# Control.net
KiCad netlist of a schematic drawn in Altium Designer
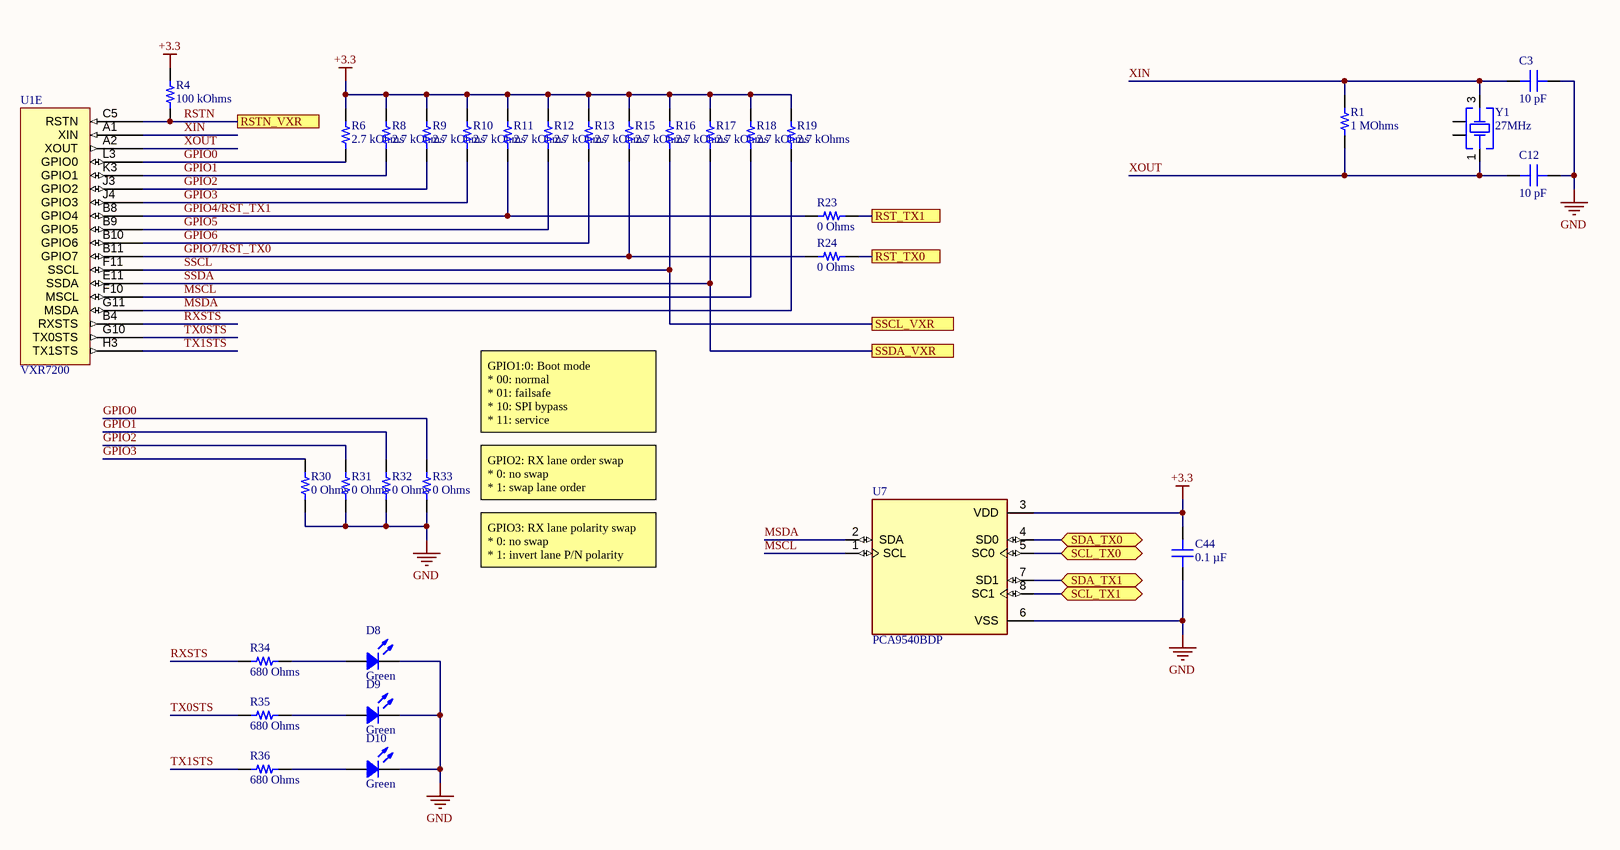
[diagram p0: Control.SchDoc]

(export (version "E")
  (design (tool "Eeschema 10.0.6"))
  (components
    (comp (ref "C3")
      (value "10 pF")
      (footprint "CAP 0201_0603")
      (description "CAP CER 10PF 25V C0G/NP0 0201")
      (fields
        (field (name "PART NUMBER") "GRM0335C1E100JA01D")
        (field (name "MANUFACTURER") "Murata Electronics")
      )
      (libsource (lib "Celestial Altium Library - altium_library") (part "Capacitor"))
    )
    (comp (ref "C12")
      (value "10 pF")
      (footprint "CAP 0201_0603")
      (description "CAP CER 10PF 25V C0G/NP0 0201")
      (fields
        (field (name "PART NUMBER") "GRM0335C1E100JA01D")
        (field (name "MANUFACTURER") "Murata Electronics")
      )
      (libsource (lib "Celestial Altium Library - altium_library") (part "Capacitor"))
    )
    (comp (ref "C44")
      (value "0.1 µF")
      (footprint "CAP 0201_0603")
      (description "CAP CER 0.1UF 25V X5R 0201")
      (fields
        (field (name "PART NUMBER") "GRM033R61E104KE14D")
        (field (name "MANUFACTURER") "Murata Electronics")
      )
      (libsource (lib "Celestial Altium Library - altium_library") (part "Capacitor"))
    )
    (comp (ref "D8")
      (value "Green")
      (footprint "LED 0603_1608 GREEN")
      (description "LED GREEN DIFFUSED 0603 SMD")
      (fields (field (name "PART NUMBER") "150060GS55040") (field (name "MANUFACTURER") "Würth Elektronik"))
      (libsource (lib "Celestial Altium Library - altium_library") (part "LED"))
    )
    (comp (ref "D9")
      (value "Green")
      (footprint "LED 0603_1608 GREEN")
      (description "LED GREEN DIFFUSED 0603 SMD")
      (fields (field (name "PART NUMBER") "150060GS55040") (field (name "MANUFACTURER") "Würth Elektronik"))
      (libsource (lib "Celestial Altium Library - altium_library") (part "LED"))
    )
    (comp (ref "D10")
      (value "Green")
      (footprint "LED 0603_1608 GREEN")
      (description "LED GREEN DIFFUSED 0603 SMD")
      (fields (field (name "PART NUMBER") "150060GS55040") (field (name "MANUFACTURER") "Würth Elektronik"))
      (libsource (lib "Celestial Altium Library - altium_library") (part "LED"))
    )
    (comp (ref "R1")
      (value "1 MOhms")
      (footprint "RES 0201_0603")
      (description "RES SMD 1M OHM 1% 1/20W 0201")
      (fields (field (name "PART NUMBER") "CRCW02011M00FKED") (field (name "MANUFACTURER") "Vishay Dale"))
      (libsource (lib "Celestial Altium Library - altium_library") (part "Resistor"))
    )
    (comp (ref "R4")
      (value "100 kOhms")
      (footprint "RES 0201_0603")
      (description "RES 100K OHM 1% 1/20W 0201 SMD")
      (fields
        (field (name "PART NUMBER") "ERJ-U01F1003C")
        (field (name "MANUFACTURER") "Panasonic Electronic Components")
      )
      (libsource (lib "Celestial Altium Library - altium_library") (part "Resistor"))
    )
    (comp (ref "R6")
      (value "2.7 kOhms")
      (footprint "RES 0201_0603")
      (description "RES 2.7K OHM 5% 1/20W 0201 SMD")
      (fields
        (field (name "PART NUMBER") "ERJ-U01J272C")
        (field (name "MANUFACTURER") "Panasonic Electronic Components")
      )
      (libsource (lib "Celestial Altium Library - altium_library") (part "Resistor"))
    )
    (comp (ref "R8")
      (value "2.7 kOhms")
      (footprint "RES 0201_0603")
      (description "RES 2.7K OHM 5% 1/20W 0201 SMD")
      (fields
        (field (name "PART NUMBER") "ERJ-U01J272C")
        (field (name "MANUFACTURER") "Panasonic Electronic Components")
      )
      (libsource (lib "Celestial Altium Library - altium_library") (part "Resistor"))
    )
    (comp (ref "R9")
      (value "2.7 kOhms")
      (footprint "RES 0201_0603")
      (description "RES 2.7K OHM 5% 1/20W 0201 SMD")
      (fields
        (field (name "PART NUMBER") "ERJ-U01J272C")
        (field (name "MANUFACTURER") "Panasonic Electronic Components")
      )
      (libsource (lib "Celestial Altium Library - altium_library") (part "Resistor"))
    )
    (comp (ref "R10")
      (value "2.7 kOhms")
      (footprint "RES 0201_0603")
      (description "RES 2.7K OHM 5% 1/20W 0201 SMD")
      (fields
        (field (name "PART NUMBER") "ERJ-U01J272C")
        (field (name "MANUFACTURER") "Panasonic Electronic Components")
      )
      (libsource (lib "Celestial Altium Library - altium_library") (part "Resistor"))
    )
    (comp (ref "R11")
      (value "2.7 kOhms")
      (footprint "RES 0201_0603")
      (description "RES 2.7K OHM 5% 1/20W 0201 SMD")
      (fields
        (field (name "PART NUMBER") "ERJ-U01J272C")
        (field (name "MANUFACTURER") "Panasonic Electronic Components")
      )
      (libsource (lib "Celestial Altium Library - altium_library") (part "Resistor"))
    )
    (comp (ref "R12")
      (value "2.7 kOhms")
      (footprint "RES 0201_0603")
      (description "RES 2.7K OHM 5% 1/20W 0201 SMD")
      (fields
        (field (name "PART NUMBER") "ERJ-U01J272C")
        (field (name "MANUFACTURER") "Panasonic Electronic Components")
      )
      (libsource (lib "Celestial Altium Library - altium_library") (part "Resistor"))
    )
    (comp (ref "R13")
      (value "2.7 kOhms")
      (footprint "RES 0201_0603")
      (description "RES 2.7K OHM 5% 1/20W 0201 SMD")
      (fields
        (field (name "PART NUMBER") "ERJ-U01J272C")
        (field (name "MANUFACTURER") "Panasonic Electronic Components")
      )
      (libsource (lib "Celestial Altium Library - altium_library") (part "Resistor"))
    )
    (comp (ref "R15")
      (value "2.7 kOhms")
      (footprint "RES 0201_0603")
      (description "RES 2.7K OHM 5% 1/20W 0201 SMD")
      (fields
        (field (name "PART NUMBER") "ERJ-U01J272C")
        (field (name "MANUFACTURER") "Panasonic Electronic Components")
      )
      (libsource (lib "Celestial Altium Library - altium_library") (part "Resistor"))
    )
    (comp (ref "R16")
      (value "2.7 kOhms")
      (footprint "RES 0201_0603")
      (description "RES 2.7K OHM 5% 1/20W 0201 SMD")
      (fields
        (field (name "PART NUMBER") "ERJ-U01J272C")
        (field (name "MANUFACTURER") "Panasonic Electronic Components")
      )
      (libsource (lib "Celestial Altium Library - altium_library") (part "Resistor"))
    )
    (comp (ref "R17")
      (value "2.7 kOhms")
      (footprint "RES 0201_0603")
      (description "RES 2.7K OHM 5% 1/20W 0201 SMD")
      (fields
        (field (name "PART NUMBER") "ERJ-U01J272C")
        (field (name "MANUFACTURER") "Panasonic Electronic Components")
      )
      (libsource (lib "Celestial Altium Library - altium_library") (part "Resistor"))
    )
    (comp (ref "R18")
      (value "2.7 kOhms")
      (footprint "RES 0201_0603")
      (description "RES 2.7K OHM 5% 1/20W 0201 SMD")
      (fields
        (field (name "PART NUMBER") "ERJ-U01J272C")
        (field (name "MANUFACTURER") "Panasonic Electronic Components")
      )
      (libsource (lib "Celestial Altium Library - altium_library") (part "Resistor"))
    )
    (comp (ref "R19")
      (value "2.7 kOhms")
      (footprint "RES 0201_0603")
      (description "RES 2.7K OHM 5% 1/20W 0201 SMD")
      (fields
        (field (name "PART NUMBER") "ERJ-U01J272C")
        (field (name "MANUFACTURER") "Panasonic Electronic Components")
      )
      (libsource (lib "Celestial Altium Library - altium_library") (part "Resistor"))
    )
    (comp (ref "R23")
      (value "0 Ohms")
      (footprint "RES 0402_1005")
      (description "RESISTOR 0402 JUMPER ZERO OHM")
      (fields (field (name "PART NUMBER") "AC0402FR-070RL") (field (name "MANUFACTURER") "Yageo"))
      (libsource (lib "Celestial Altium Library - altium_library") (part "Resistor"))
    )
    (comp (ref "R24")
      (value "0 Ohms")
      (footprint "RES 0402_1005")
      (description "RESISTOR 0402 JUMPER ZERO OHM")
      (fields (field (name "PART NUMBER") "AC0402FR-070RL") (field (name "MANUFACTURER") "Yageo"))
      (libsource (lib "Celestial Altium Library - altium_library") (part "Resistor"))
    )
    (comp (ref "R30")
      (value "0 Ohms")
      (footprint "RES 0402_1005")
      (description "RESISTOR 0402 JUMPER ZERO OHM")
      (fields (field (name "PART NUMBER") "AC0402FR-070RL") (field (name "MANUFACTURER") "Yageo"))
      (libsource (lib "Celestial Altium Library - altium_library") (part "Resistor"))
    )
    (comp (ref "R31")
      (value "0 Ohms")
      (footprint "RES 0402_1005")
      (description "RESISTOR 0402 JUMPER ZERO OHM")
      (fields (field (name "PART NUMBER") "AC0402FR-070RL") (field (name "MANUFACTURER") "Yageo"))
      (libsource (lib "Celestial Altium Library - altium_library") (part "Resistor"))
    )
    (comp (ref "R32")
      (value "0 Ohms")
      (footprint "RES 0402_1005")
      (description "RESISTOR 0402 JUMPER ZERO OHM")
      (fields (field (name "PART NUMBER") "AC0402FR-070RL") (field (name "MANUFACTURER") "Yageo"))
      (libsource (lib "Celestial Altium Library - altium_library") (part "Resistor"))
    )
    (comp (ref "R33")
      (value "0 Ohms")
      (footprint "RES 0402_1005")
      (description "RESISTOR 0402 JUMPER ZERO OHM")
      (fields (field (name "PART NUMBER") "AC0402FR-070RL") (field (name "MANUFACTURER") "Yageo"))
      (libsource (lib "Celestial Altium Library - altium_library") (part "Resistor"))
    )
    (comp (ref "R34")
      (value "680 Ohms")
      (footprint "RES 0402_1005")
      (description "RES SMD 680 OHM 1% 1/5W 0402")
      (fields (field (name "PART NUMBER") "RCS0402680RFKED") (field (name "MANUFACTURER") "Vishay Dale"))
      (libsource (lib "Celestial Altium Library - altium_library") (part "Resistor"))
    )
    (comp (ref "R35")
      (value "680 Ohms")
      (footprint "RES 0402_1005")
      (description "RES SMD 680 OHM 1% 1/5W 0402")
      (fields (field (name "PART NUMBER") "RCS0402680RFKED") (field (name "MANUFACTURER") "Vishay Dale"))
      (libsource (lib "Celestial Altium Library - altium_library") (part "Resistor"))
    )
    (comp (ref "R36")
      (value "680 Ohms")
      (footprint "RES 0402_1005")
      (description "RES SMD 680 OHM 1% 1/5W 0402")
      (fields (field (name "PART NUMBER") "RCS0402680RFKED") (field (name "MANUFACTURER") "Vishay Dale"))
      (libsource (lib "Celestial Altium Library - altium_library") (part "Resistor"))
    )
    (comp (ref "U1")
      (value "VXR7200")
      (footprint "BGA100P9X9-81A")
      (description "VXR7200 DP to MIPI-DSI bridge")
      (libsource (lib "SimulaVR") (part "VXR7200-Symbol-1"))
    )
    (comp (ref "U7")
      (value "PCA9540BDP")
      (footprint "PCA9540BDP:SOP65P490X110-8N")
      (description "2-Channel IﾂｲC Multiplexer Interface 8-TSSOP")
      (fields (field (name "MF") "{'manufacturer': u'NXP USA'}"))
      (libsource (lib "PCA9540BDP") (part "PCA9540BDP"))
    )
    (comp (ref "Y1")
      (value "27MHz")
      (footprint "WE-XTAL_CFPX-218")
      (description "WE-XTAL Quartz Crystal, SMT, CFPX-218, 27MHz, +/-10ppm")
      (fields
        (field (name "MANUFACTURER PART NUMBER") "830108208409")
        (field (name "MANUFACTURER") "Wurth Elektronik")
      )
      (libsource (lib "Altium_WE-XTAL (rev21a)") (part "830108208409"))
    )
  )
  (nets
    (net (code "1") (name "+3.3") (class "Default")
      (node (ref "C44") (pin "2") (pinfunction "2_2") (pintype "passive"))
      (node (ref "R10") (pin "2") (pinfunction "2_2") (pintype "passive"))
      (node (ref "R11") (pin "2") (pinfunction "2_2") (pintype "passive"))
      (node (ref "R12") (pin "2") (pinfunction "2_2") (pintype "passive"))
      (node (ref "R13") (pin "2") (pinfunction "2_2") (pintype "passive"))
      (node (ref "R15") (pin "2") (pinfunction "2_2") (pintype "passive"))
      (node (ref "R16") (pin "2") (pinfunction "2_2") (pintype "passive"))
      (node (ref "R17") (pin "2") (pinfunction "2_2") (pintype "passive"))
      (node (ref "R18") (pin "2") (pinfunction "2_2") (pintype "passive"))
      (node (ref "R19") (pin "2") (pinfunction "2_2") (pintype "passive"))
      (node (ref "R4") (pin "2") (pinfunction "2_2") (pintype "passive"))
      (node (ref "R6") (pin "2") (pinfunction "2_2") (pintype "passive"))
      (node (ref "R8") (pin "2") (pinfunction "2_2") (pintype "passive"))
      (node (ref "R9") (pin "2") (pinfunction "2_2") (pintype "passive"))
      (node (ref "U7") (pin "3") (pinfunction "VDD_3") (pintype "power_in"))
    )
    (net (code "2") (name "/GPIO0") (class "Default")
      (node (ref "R33") (pin "2") (pinfunction "2_2") (pintype "passive"))
      (node (ref "R6") (pin "1") (pinfunction "1_1") (pintype "passive"))
      (node (ref "U1") (pin "L3") (pinfunction "GPIO0_L3") (pintype "bidirectional"))
    )
    (net (code "3") (name "/GPIO1") (class "Default")
      (node (ref "R32") (pin "2") (pinfunction "2_2") (pintype "passive"))
      (node (ref "R8") (pin "1") (pinfunction "1_1") (pintype "passive"))
      (node (ref "U1") (pin "K3") (pinfunction "GPIO1_K3") (pintype "bidirectional"))
    )
    (net (code "4") (name "/GPIO2") (class "Default")
      (node (ref "R31") (pin "2") (pinfunction "2_2") (pintype "passive"))
      (node (ref "R9") (pin "1") (pinfunction "1_1") (pintype "passive"))
      (node (ref "U1") (pin "J3") (pinfunction "GPIO2_J3") (pintype "bidirectional"))
    )
    (net (code "5") (name "/GPIO3") (class "Default")
      (node (ref "R10") (pin "1") (pinfunction "1_1") (pintype "passive"))
      (node (ref "R30") (pin "2") (pinfunction "2_2") (pintype "passive"))
      (node (ref "U1") (pin "J4") (pinfunction "GPIO3_J4") (pintype "bidirectional"))
    )
    (net (code "6") (name "/GPIO4{slash}RST_TX1") (class "Default")
      (node (ref "R11") (pin "1") (pinfunction "1_1") (pintype "passive"))
      (node (ref "R23") (pin "2") (pinfunction "2_2") (pintype "passive"))
      (node (ref "U1") (pin "B8") (pinfunction "GPIO4_B8") (pintype "bidirectional"))
    )
    (net (code "7") (name "/GPIO5") (class "Default")
      (node (ref "R12") (pin "1") (pinfunction "1_1") (pintype "passive"))
      (node (ref "U1") (pin "B9") (pinfunction "GPIO5_B9") (pintype "bidirectional"))
    )
    (net (code "8") (name "/GPIO6") (class "Default")
      (node (ref "R13") (pin "1") (pinfunction "1_1") (pintype "passive"))
      (node (ref "U1") (pin "B10") (pinfunction "GPIO6_B10") (pintype "bidirectional"))
    )
    (net (code "9") (name "/GPIO7{slash}RST_TX0") (class "Default")
      (node (ref "R15") (pin "1") (pinfunction "1_1") (pintype "passive"))
      (node (ref "R24") (pin "2") (pinfunction "2_2") (pintype "passive"))
      (node (ref "U1") (pin "B11") (pinfunction "GPIO7_B11") (pintype "bidirectional"))
    )
    (net (code "10") (name "/MSCL") (class "Default")
      (node (ref "R18") (pin "1") (pinfunction "1_1") (pintype "passive"))
      (node (ref "U1") (pin "F10") (pinfunction "MSCL_F10") (pintype "bidirectional"))
      (node (ref "U7") (pin "1") (pinfunction "SCL_1") (pintype "bidirectional"))
    )
    (net (code "11") (name "/MSDA") (class "Default")
      (node (ref "R19") (pin "1") (pinfunction "1_1") (pintype "passive"))
      (node (ref "U1") (pin "G11") (pinfunction "MSDA_G11") (pintype "bidirectional"))
      (node (ref "U7") (pin "2") (pinfunction "SDA_2") (pintype "bidirectional"))
    )
    (net (code "12") (name "/RSTN") (class "Default")
      (node (ref "R4") (pin "1") (pinfunction "1_1") (pintype "passive"))
      (node (ref "U1") (pin "C5") (pinfunction "RSTN_C5") (pintype "input"))
    )
    (net (code "13") (name "/RST_TX0") (class "Default")
      (node (ref "R24") (pin "1") (pinfunction "1_1") (pintype "passive"))
    )
    (net (code "14") (name "/RST_TX1") (class "Default")
      (node (ref "R23") (pin "1") (pinfunction "1_1") (pintype "passive"))
    )
    (net (code "15") (name "/RXSTS") (class "Default")
      (node (ref "R34") (pin "1") (pinfunction "1_1") (pintype "passive"))
      (node (ref "U1") (pin "B4") (pinfunction "RXSTS_B4") (pintype "output"))
    )
    (net (code "16") (name "/SCL_TX0") (class "Default")
      (node (ref "U7") (pin "5") (pinfunction "SC0_5") (pintype "bidirectional"))
    )
    (net (code "17") (name "/SCL_TX1") (class "Default")
      (node (ref "U7") (pin "8") (pinfunction "SC1_8") (pintype "bidirectional"))
    )
    (net (code "18") (name "/SDA_TX0") (class "Default")
      (node (ref "U7") (pin "4") (pinfunction "SD0_4") (pintype "bidirectional"))
    )
    (net (code "19") (name "/SDA_TX1") (class "Default")
      (node (ref "U7") (pin "7") (pinfunction "SD1_7") (pintype "bidirectional"))
    )
    (net (code "20") (name "/SSCL") (class "Default")
      (node (ref "R16") (pin "1") (pinfunction "1_1") (pintype "passive"))
      (node (ref "U1") (pin "F11") (pinfunction "SSCL_F11") (pintype "bidirectional"))
    )
    (net (code "21") (name "/SSDA") (class "Default")
      (node (ref "R17") (pin "1") (pinfunction "1_1") (pintype "passive"))
      (node (ref "U1") (pin "E11") (pinfunction "SSDA_E11") (pintype "bidirectional"))
    )
    (net (code "22") (name "/TX0STS") (class "Default")
      (node (ref "R35") (pin "1") (pinfunction "1_1") (pintype "passive"))
      (node (ref "U1") (pin "G10") (pinfunction "TX0STS_G10") (pintype "output"))
    )
    (net (code "23") (name "/TX1STS") (class "Default")
      (node (ref "R36") (pin "1") (pinfunction "1_1") (pintype "passive"))
      (node (ref "U1") (pin "H3") (pinfunction "TX1STS_H3") (pintype "output"))
    )
    (net (code "24") (name "/XIN") (class "Default")
      (node (ref "C3") (pin "1") (pinfunction "1_1") (pintype "passive"))
      (node (ref "R1") (pin "2") (pinfunction "2_2") (pintype "passive"))
      (node (ref "U1") (pin "A1") (pinfunction "XIN_A1") (pintype "input"))
      (node (ref "Y1") (pin "3") (pinfunction "Crystal_3") (pintype "passive"))
    )
    (net (code "25") (name "/XOUT") (class "Default")
      (node (ref "C12") (pin "1") (pinfunction "1_1") (pintype "passive"))
      (node (ref "R1") (pin "1") (pinfunction "1_1") (pintype "passive"))
      (node (ref "U1") (pin "A2") (pinfunction "XOUT_A2") (pintype "output"))
      (node (ref "Y1") (pin "1") (pinfunction "Crystal_1") (pintype "passive"))
    )
    (net (code "26") (name "GND") (class "Default")
      (node (ref "C12") (pin "2") (pinfunction "2_2") (pintype "passive"))
      (node (ref "C3") (pin "2") (pinfunction "2_2") (pintype "passive"))
      (node (ref "C44") (pin "1") (pinfunction "1_1") (pintype "passive"))
      (node (ref "D10") (pin "2") (pinfunction "2_2") (pintype "passive"))
      (node (ref "D8") (pin "2") (pinfunction "2_2") (pintype "passive"))
      (node (ref "D9") (pin "2") (pinfunction "2_2") (pintype "passive"))
      (node (ref "R30") (pin "1") (pinfunction "1_1") (pintype "passive"))
      (node (ref "R31") (pin "1") (pinfunction "1_1") (pintype "passive"))
      (node (ref "R32") (pin "1") (pinfunction "1_1") (pintype "passive"))
      (node (ref "R33") (pin "1") (pinfunction "1_1") (pintype "passive"))
      (node (ref "U7") (pin "6") (pinfunction "VSS_6") (pintype "power_in"))
    )
    (net (code "27") (name "Net-(D8-Pad1)") (class "Default")
      (node (ref "D8") (pin "1") (pinfunction "1_1") (pintype "passive"))
      (node (ref "R34") (pin "2") (pinfunction "2_2") (pintype "passive"))
    )
    (net (code "28") (name "Net-(D9-Pad1)") (class "Default")
      (node (ref "D9") (pin "1") (pinfunction "1_1") (pintype "passive"))
      (node (ref "R35") (pin "2") (pinfunction "2_2") (pintype "passive"))
    )
    (net (code "29") (name "Net-(D10-Pad1)") (class "Default")
      (node (ref "D10") (pin "1") (pinfunction "1_1") (pintype "passive"))
      (node (ref "R36") (pin "2") (pinfunction "2_2") (pintype "passive"))
    )
    (net (code "30") (name "unconnected-(Y1-GND-Pad2)") (class "Default")
      (node (ref "Y1") (pin "2") (pinfunction "GND_2") (pintype "passive"))
    )
    (net (code "31") (name "unconnected-(Y1-GND-Pad4)") (class "Default")
      (node (ref "Y1") (pin "4") (pinfunction "GND_4") (pintype "passive"))
    )
  )
)
